# BaseBand.net
KiCad netlist of a schematic drawn in Altium Designer
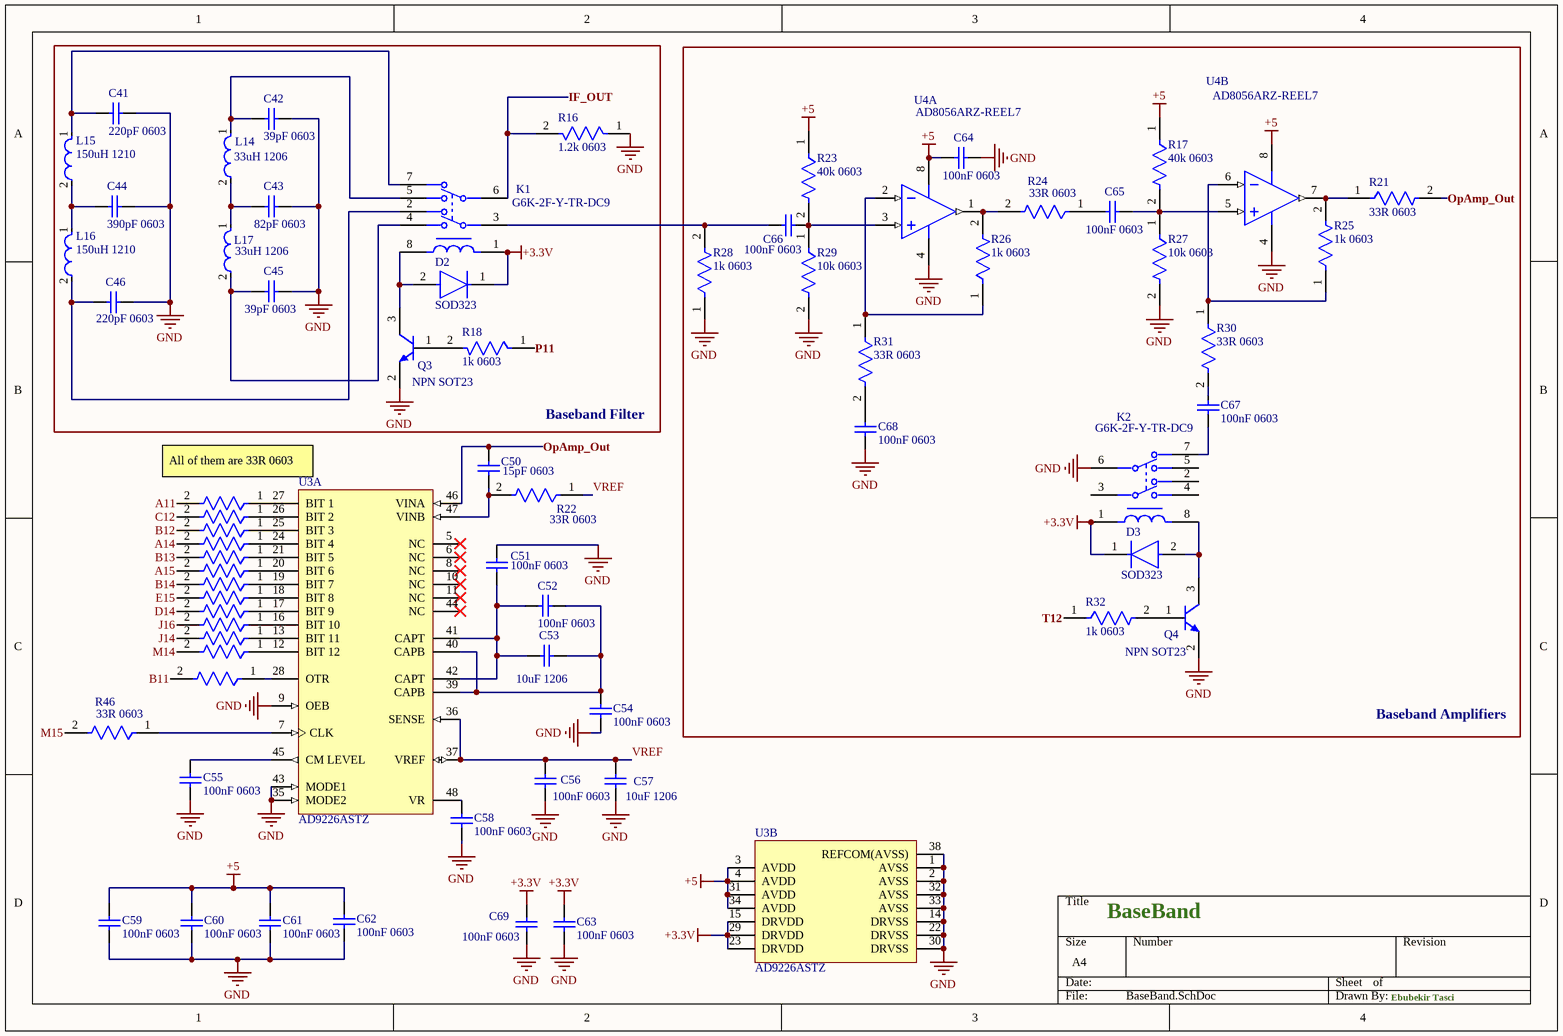
[diagram p0: BaseBand.SchDoc]

(export (version "E")
  (design (tool "Eeschema 10.0.6"))
  (components
    (comp (ref "C41")
      (value "220pF 0603")
      (footprint "CAPC1608X92X38LL15T08")
      (fields (field (name "MANUFACTURER") "Vitramon") (field (name "PART NUMBER") "VJ0603A101FXAAC"))
      (libsource (lib "Altium Content Vault") (part "CAP"))
    )
    (comp (ref "C42")
      (value "39pF 0603")
      (footprint "CAPC1608X92X38LL15T08")
      (fields (field (name "MANUFACTURER") "Vitramon") (field (name "PART NUMBER") "VJ0603A101FXAAC"))
      (libsource (lib "Altium Content Vault") (part "CAP"))
    )
    (comp (ref "C43")
      (value "82pF 0603")
      (footprint "CAPC1608X92X38LL15T08")
      (fields (field (name "MANUFACTURER") "Vitramon") (field (name "PART NUMBER") "VJ0603A101FXAAC"))
      (libsource (lib "Altium Content Vault") (part "CAP"))
    )
    (comp (ref "C44")
      (value "390pF 0603")
      (footprint "CAPC1608X92X38LL15T08")
      (fields (field (name "MANUFACTURER") "Vitramon") (field (name "PART NUMBER") "VJ0603A101FXAAC"))
      (libsource (lib "Altium Content Vault") (part "CAP"))
    )
    (comp (ref "C45")
      (value "39pF 0603")
      (footprint "CAPC1608X92X38LL15T08")
      (fields (field (name "MANUFACTURER") "Vitramon") (field (name "PART NUMBER") "VJ0603A101FXAAC"))
      (libsource (lib "Altium Content Vault") (part "CAP"))
    )
    (comp (ref "C46")
      (value "220pF 0603")
      (footprint "CAPC1608X92X38LL15T08")
      (fields (field (name "MANUFACTURER") "Vitramon") (field (name "PART NUMBER") "VJ0603A101FXAAC"))
      (libsource (lib "Altium Content Vault") (part "CAP"))
    )
    (comp (ref "C50")
      (value "15pF 0603")
      (footprint "CAPC1608X92X38LL15T08")
      (fields (field (name "MANUFACTURER") "Vitramon") (field (name "PART NUMBER") "VJ0603A101FXAAC"))
      (libsource (lib "Altium Content Vault") (part "CAP"))
    )
    (comp (ref "C51")
      (value "100nF 0603")
      (footprint "CAPC0603(1608)100_L")
      (description "CAP 100nF 16V ±0.1pF 0603 (1608 Metric) Thickness 1mm SMD")
      (fields (field (name "TOLERANCE") "Â±0.1pF"))
      (libsource (lib "Altium Content Vault") (part "CAP"))
    )
    (comp (ref "C52")
      (value "100nF 0603")
      (footprint "CAPC0603(1608)100_L")
      (description "CAP 100nF 16V ±0.1pF 0603 (1608 Metric) Thickness 1mm SMD")
      (fields (field (name "TOLERANCE") "Â±0.1pF"))
      (libsource (lib "Altium Content Vault") (part "CAP"))
    )
    (comp (ref "C53")
      (value "10uF 1206")
      (footprint "CAPC1206(3216)190_M")
      (description "CAP 10uF 16V ±5% 1206 (3216 Metric) Thickness 1.9mm SMD")
      (fields (field (name "TOLERANCE") "Â±5%"))
      (libsource (lib "Altium Content Vault") (part "CAP"))
    )
    (comp (ref "C54")
      (value "100nF 0603")
      (footprint "CAPC0603(1608)100_L")
      (description "CAP 100nF 16V ±0.1pF 0603 (1608 Metric) Thickness 1mm SMD")
      (fields (field (name "TOLERANCE") "Â±0.1pF"))
      (libsource (lib "Altium Content Vault") (part "CAP"))
    )
    (comp (ref "C55")
      (value "100nF 0603")
      (footprint "CAPC0603(1608)100_L")
      (description "CAP 100nF 16V ±0.1pF 0603 (1608 Metric) Thickness 1mm SMD")
      (fields (field (name "TOLERANCE") "Â±0.1pF"))
      (libsource (lib "Altium Content Vault") (part "CAP"))
    )
    (comp (ref "C56")
      (value "100nF 0603")
      (footprint "CAPC0603(1608)100_L")
      (description "CAP 100nF 16V ±0.1pF 0603 (1608 Metric) Thickness 1mm SMD")
      (fields (field (name "TOLERANCE") "Â±0.1pF"))
      (libsource (lib "Altium Content Vault") (part "CAP"))
    )
    (comp (ref "C57")
      (value "10uF 1206")
      (footprint "CAPC1206(3216)190_M")
      (description "CAP 10uF 16V ±5% 1206 (3216 Metric) Thickness 1.9mm SMD")
      (fields (field (name "TOLERANCE") "Â±5%"))
      (libsource (lib "Altium Content Vault") (part "CAP"))
    )
    (comp (ref "C58")
      (value "100nF 0603")
      (footprint "CAPC0603(1608)100_L")
      (description "CAP 100nF 16V ±0.1pF 0603 (1608 Metric) Thickness 1mm SMD")
      (fields (field (name "TOLERANCE") "Â±0.1pF"))
      (libsource (lib "Altium Content Vault") (part "CAP"))
    )
    (comp (ref "C59")
      (value "100nF 0603")
      (footprint "CAPC0603(1608)100_L")
      (description "CAP 100nF 16V ±0.1pF 0603 (1608 Metric) Thickness 1mm SMD")
      (fields (field (name "TOLERANCE") "Â±0.1pF"))
      (libsource (lib "Altium Content Vault") (part "CAP"))
    )
    (comp (ref "C60")
      (value "100nF 0603")
      (footprint "CAPC0603(1608)100_L")
      (description "CAP 100nF 16V ±0.1pF 0603 (1608 Metric) Thickness 1mm SMD")
      (fields (field (name "TOLERANCE") "Â±0.1pF"))
      (libsource (lib "Altium Content Vault") (part "CAP"))
    )
    (comp (ref "C61")
      (value "100nF 0603")
      (footprint "CAPC0603(1608)100_L")
      (description "CAP 100nF 16V ±0.1pF 0603 (1608 Metric) Thickness 1mm SMD")
      (fields (field (name "TOLERANCE") "Â±0.1pF"))
      (libsource (lib "Altium Content Vault") (part "CAP"))
    )
    (comp (ref "C62")
      (value "100nF 0603")
      (footprint "CAPC0603(1608)100_L")
      (description "CAP 100nF 16V ±0.1pF 0603 (1608 Metric) Thickness 1mm SMD")
      (fields (field (name "TOLERANCE") "Â±0.1pF"))
      (libsource (lib "Altium Content Vault") (part "CAP"))
    )
    (comp (ref "C63")
      (value "100nF 0603")
      (footprint "CAPC0603(1608)100_L")
      (description "CAP 100nF 16V ±0.1pF 0603 (1608 Metric) Thickness 1mm SMD")
      (fields (field (name "TOLERANCE") "Â±0.1pF"))
      (libsource (lib "Altium Content Vault") (part "CAP"))
    )
    (comp (ref "C64")
      (value "100nF 0603")
      (footprint "CAPC0603(1608)100_L")
      (description "CAP 100nF 16V ±0.1pF 0603 (1608 Metric) Thickness 1mm SMD")
      (fields (field (name "TOLERANCE") "Â±0.1pF"))
      (libsource (lib "Altium Content Vault") (part "CAP"))
    )
    (comp (ref "C65")
      (value "100nF 0603")
      (footprint "CAPC0603(1608)100_L")
      (description "CAP 100nF 16V ±0.1pF 0603 (1608 Metric) Thickness 1mm SMD")
      (fields (field (name "TOLERANCE") "Â±0.1pF"))
      (libsource (lib "Altium Content Vault") (part "CAP"))
    )
    (comp (ref "C66")
      (value "100nF 0603")
      (footprint "CAPC0603(1608)100_L")
      (description "CAP 100nF 16V ±0.1pF 0603 (1608 Metric) Thickness 1mm SMD")
      (fields (field (name "TOLERANCE") "Â±0.1pF"))
      (libsource (lib "Altium Content Vault") (part "CAP"))
    )
    (comp (ref "C67")
      (value "100nF 0603")
      (footprint "CAPC0603(1608)100_L")
      (description "CAP 100nF 16V ±0.1pF 0603 (1608 Metric) Thickness 1mm SMD")
      (fields (field (name "TOLERANCE") "Â±0.1pF"))
      (libsource (lib "Altium Content Vault") (part "CAP"))
    )
    (comp (ref "C68")
      (value "100nF 0603")
      (footprint "CAPC0603(1608)100_L")
      (description "CAP 100nF 16V ±0.1pF 0603 (1608 Metric) Thickness 1mm SMD")
      (fields (field (name "TOLERANCE") "Â±0.1pF"))
      (libsource (lib "Altium Content Vault") (part "CAP"))
    )
    (comp (ref "C69")
      (value "100nF 0603")
      (footprint "CAPC0603(1608)100_L")
      (description "CAP 100nF 16V ±0.1pF 0603 (1608 Metric) Thickness 1mm SMD")
      (fields (field (name "TOLERANCE") "Â±0.1pF"))
      (libsource (lib "Altium Content Vault") (part "CAP"))
    )
    (comp (ref "D2")
      (value "SOD323")
      (footprint "FP-SOD323F-MFG")
      (description "DIODE GEN PURP 100V 250MA SOD323")
      (fields
        (field (name "MANUFACTURER PART NUMBER") "1N4148WSF-7")
        (field (name "MANUFACTURER") "Diodes Inc.")
      )
      (libsource (lib "Altium Content Vault") (part "d7152d700b627762746794eb795d46e"))
    )
    (comp (ref "D3")
      (value "SOD323")
      (footprint "FP-SOD323F-MFG")
      (description "DIODE GEN PURP 100V 250MA SOD323")
      (fields
        (field (name "MANUFACTURER PART NUMBER") "1N4148WSF-7")
        (field (name "MANUFACTURER") "Diodes Inc.")
      )
      (libsource (lib "Altium Content Vault") (part "d7152d700b627762746794eb795d46e"))
    )
    (comp (ref "K1")
      (value "G6K-2F-Y-TR-DC9")
      (footprint "FP-G6K-2F-Y-TR-DC9-MFG")
      (description "RELAY TELECOM DPDT 1A 9VDC")
      (libsource (lib "") (part "58c38101009d5ebbf9054263c5b66d6_1"))
    )
    (comp (ref "K2")
      (value "G6K-2F-Y-TR-DC9")
      (footprint "FP-G6K-2F-Y-TR-DC9-MFG")
      (description "RELAY TELECOM DPDT 1A 9VDC")
      (libsource (lib "Altium Content Vault") (part "58c38101009d5ebbf9054263c5b66d6"))
    )
    (comp (ref "L14")
      (value "33uH 1206")
      (footprint "FP-CB3225-IPC_A")
      (description "SMD Inductors 33uH ±10% 0.57A 0.533Ω 1210")
      (fields (field (name "TOLERANCE") "10%"))
      (libsource (lib "Altium Content Vault") (part "725321dda6339637d4d059423bc1c3c"))
    )
    (comp (ref "L15")
      (value "150uH 1210")
      (footprint "FP-LQH32CH_23-MFG")
      (description "Wire Wound Ferrite Inductor for General Circuits 150μH ±10% 9.3Ω 70mA 1210")
      (fields (field (name "TOLERANCE") "10%"))
      (libsource (lib "Altium Content Vault") (part "725321dda6339637d4d059423bc1c3c"))
    )
    (comp (ref "L16")
      (value "150uH 1210")
      (footprint "FP-LQH32CH_23-MFG")
      (description "Wire Wound Ferrite Inductor for General Circuits 150μH ±10% 9.3Ω 70mA 1210")
      (fields (field (name "TOLERANCE") "10%"))
      (libsource (lib "Altium Content Vault") (part "725321dda6339637d4d059423bc1c3c"))
    )
    (comp (ref "L17")
      (value "33uH 1206")
      (footprint "FP-CB3225-IPC_A")
      (description "SMD Inductors 33uH ±10% 0.57A 0.533Ω 1210")
      (fields (field (name "TOLERANCE") "10%"))
      (libsource (lib "Altium Content Vault") (part "725321dda6339637d4d059423bc1c3c"))
    )
    (comp (ref "Q3")
      (value "NPN SOT23")
      (footprint "ONSC-SOT-23-3-318-08_V")
      (description "VHF / UHF Transistor, NPN Silicon, 3-Pin SOT-23, Pb-Free, Tape and Reel")
      (fields (field (name "MANUFACTURER") "On Semiconductor") (field (name "PARTNUMBER") "NSVMMBTH10LT1G"))
      (libsource (lib "Altium Content Vault") (part "ONSC-NPN-B1E2C3-3"))
    )
    (comp (ref "Q4")
      (value "NPN SOT23")
      (footprint "ONSC-SOT-23-3-318-08_V")
      (description "VHF / UHF Transistor, NPN Silicon, 3-Pin SOT-23, Pb-Free, Tape and Reel")
      (fields (field (name "MANUFACTURER") "On Semiconductor") (field (name "PARTNUMBER") "NSVMMBTH10LT1G"))
      (libsource (lib "Altium Content Vault") (part "ONSC-NPN-B1E2C3-3"))
    )
    (comp (ref "R16")
      (value "1.2k 0603")
      (footprint "FP-CPF0603-MFG")
      (description "RES SMD 1.2kΩ 0.1% 1/16W 0603")
      (fields
        (field (name "OCTOPART") "https://octopart.com/cpf0603b430re1-te+connectivity-22738753")
        (field (name "MANUFACTURER PART NUMBER") "CPF0603B430RE1")
      )
      (libsource (lib "Altium Content Vault") (part "1029c3af85768c4190bb7ad29bc67b5"))
    )
    (comp (ref "R17")
      (value "40k 0603")
      (footprint "FP-CPF0603-MFG")
      (description "RES SMD 40kΩ 0.1% 1/16W 0603")
      (fields
        (field (name "OCTOPART") "https://octopart.com/cpf0603b430re1-te+connectivity-22738753")
        (field (name "MANUFACTURER PART NUMBER") "CPF0603B430RE1")
      )
      (libsource (lib "Altium Content Vault") (part "1029c3af85768c4190bb7ad29bc67b5"))
    )
    (comp (ref "R18")
      (value "1k 0603")
      (footprint "FP-CPF0603-MFG")
      (description "RES SMD 1kΩ 0.1% 1/16W 0603")
      (fields
        (field (name "OCTOPART") "https://octopart.com/cpf0603b430re1-te+connectivity-22738753")
        (field (name "MANUFACTURER PART NUMBER") "CPF0603B430RE1")
      )
      (libsource (lib "Altium Content Vault") (part "1029c3af85768c4190bb7ad29bc67b5"))
    )
    (comp (ref "R21")
      (value "33R 0603")
      (footprint "FP-CPF0603-MFG")
      (description "RES SMD 33Ω 0.1% 1/16W 0603")
      (fields (field (name "TOLERANCE") "0.1%") (field (name "MANUFACTURER") "TE Connectivity"))
      (libsource (lib "Altium Content Vault") (part "1029c3af85768c4190bb7ad29bc67b5"))
    )
    (comp (ref "R22")
      (value "33R 0603")
      (footprint "FP-CPF0603-MFG")
      (description "RES SMD 33Ω 0.1% 1/16W 0603")
      (fields (field (name "TOLERANCE") "0.1%") (field (name "MANUFACTURER") "TE Connectivity"))
      (libsource (lib "Altium Content Vault") (part "1029c3af85768c4190bb7ad29bc67b5"))
    )
    (comp (ref "R23")
      (value "40k 0603")
      (footprint "FP-CPF0603-MFG")
      (description "RES SMD 40kΩ 0.1% 1/16W 0603")
      (fields
        (field (name "OCTOPART") "https://octopart.com/cpf0603b430re1-te+connectivity-22738753")
        (field (name "MANUFACTURER PART NUMBER") "CPF0603B430RE1")
      )
      (libsource (lib "Altium Content Vault") (part "1029c3af85768c4190bb7ad29bc67b5"))
    )
    (comp (ref "R24")
      (value "33R 0603")
      (footprint "FP-CPF0603-MFG")
      (description "RES SMD 33Ω 0.1% 1/16W 0603")
      (fields
        (field (name "OCTOPART") "https://octopart.com/cpf0603b430re1-te+connectivity-22738753")
        (field (name "MANUFACTURER PART NUMBER") "CPF0603B430RE1")
      )
      (libsource (lib "Altium Content Vault") (part "1029c3af85768c4190bb7ad29bc67b5"))
    )
    (comp (ref "R25")
      (value "1k 0603")
      (footprint "FP-CPF0603-MFG")
      (description "RES SMD 1kΩ 0.1% 1/16W 0603")
      (fields
        (field (name "OCTOPART") "https://octopart.com/cpf0603b430re1-te+connectivity-22738753")
        (field (name "MANUFACTURER PART NUMBER") "CPF0603B430RE1")
      )
      (libsource (lib "Altium Content Vault") (part "1029c3af85768c4190bb7ad29bc67b5"))
    )
    (comp (ref "R26")
      (value "1k 0603")
      (footprint "FP-CPF0603-MFG")
      (description "RES SMD 1kΩ 0.1% 1/16W 0603")
      (fields
        (field (name "OCTOPART") "https://octopart.com/cpf0603b430re1-te+connectivity-22738753")
        (field (name "MANUFACTURER PART NUMBER") "CPF0603B430RE1")
      )
      (libsource (lib "Altium Content Vault") (part "1029c3af85768c4190bb7ad29bc67b5"))
    )
    (comp (ref "R27")
      (value "10k 0603")
      (footprint "FP-CPF0603-MFG")
      (description "RES SMD 10kΩ 0.1% 1/16W 0603")
      (fields
        (field (name "OCTOPART") "https://octopart.com/cpf0603b430re1-te+connectivity-22738753")
        (field (name "MANUFACTURER PART NUMBER") "CPF0603B430RE1")
      )
      (libsource (lib "Altium Content Vault") (part "1029c3af85768c4190bb7ad29bc67b5"))
    )
    (comp (ref "R28")
      (value "1k 0603")
      (footprint "FP-CPF0603-MFG")
      (description "RES SMD 1kΩ 0.1% 1/16W 0603")
      (fields
        (field (name "OCTOPART") "https://octopart.com/cpf0603b430re1-te+connectivity-22738753")
        (field (name "MANUFACTURER PART NUMBER") "CPF0603B430RE1")
      )
      (libsource (lib "Altium Content Vault") (part "1029c3af85768c4190bb7ad29bc67b5"))
    )
    (comp (ref "R29")
      (value "10k 0603")
      (footprint "FP-CPF0603-MFG")
      (description "RES SMD 10kΩ 0.1% 1/16W 0603")
      (fields
        (field (name "OCTOPART") "https://octopart.com/cpf0603b430re1-te+connectivity-22738753")
        (field (name "MANUFACTURER PART NUMBER") "CPF0603B430RE1")
      )
      (libsource (lib "Altium Content Vault") (part "1029c3af85768c4190bb7ad29bc67b5"))
    )
    (comp (ref "R30")
      (value "33R 0603")
      (footprint "FP-CPF0603-MFG")
      (description "RES SMD 33Ω 0.1% 1/16W 0603")
      (fields
        (field (name "OCTOPART") "https://octopart.com/cpf0603b430re1-te+connectivity-22738753")
        (field (name "MANUFACTURER PART NUMBER") "CPF0603B430RE1")
      )
      (libsource (lib "Altium Content Vault") (part "1029c3af85768c4190bb7ad29bc67b5"))
    )
    (comp (ref "R31")
      (value "33R 0603")
      (footprint "FP-CPF0603-MFG")
      (description "RES SMD 33Ω 0.1% 1/16W 0603")
      (fields
        (field (name "OCTOPART") "https://octopart.com/cpf0603b430re1-te+connectivity-22738753")
        (field (name "MANUFACTURER PART NUMBER") "CPF0603B430RE1")
      )
      (libsource (lib "Altium Content Vault") (part "1029c3af85768c4190bb7ad29bc67b5"))
    )
    (comp (ref "R32")
      (value "1k 0603")
      (footprint "FP-CPF0603-MFG")
      (description "RES SMD 1kΩ 0.1% 1/16W 0603")
      (fields
        (field (name "OCTOPART") "https://octopart.com/cpf0603b430re1-te+connectivity-22738753")
        (field (name "MANUFACTURER PART NUMBER") "CPF0603B430RE1")
      )
      (libsource (lib "Altium Content Vault") (part "1029c3af85768c4190bb7ad29bc67b5"))
    )
    (comp (ref "R33")
      (value "33R 0603")
      (footprint "FP-CPF0603-MFG")
      (description "RES SMD 33Ω 0.1% 1/16W 0603")
      (fields
        (field (name "OCTOPART") "https://octopart.com/cpf0603b430re1-te+connectivity-22738753")
        (field (name "MANUFACTURER PART NUMBER") "CPF0603B430RE1")
      )
      (libsource (lib "Altium Content Vault") (part "1029c3af85768c4190bb7ad29bc67b5"))
    )
    (comp (ref "R34")
      (value "33R 0603")
      (footprint "FP-CPF0603-MFG")
      (description "RES SMD 33Ω 0.1% 1/16W 0603")
      (fields
        (field (name "OCTOPART") "https://octopart.com/cpf0603b430re1-te+connectivity-22738753")
        (field (name "MANUFACTURER PART NUMBER") "CPF0603B430RE1")
      )
      (libsource (lib "Altium Content Vault") (part "1029c3af85768c4190bb7ad29bc67b5"))
    )
    (comp (ref "R35")
      (value "33R 0603")
      (footprint "FP-CPF0603-MFG")
      (description "RES SMD 33Ω 0.1% 1/16W 0603")
      (fields
        (field (name "OCTOPART") "https://octopart.com/cpf0603b430re1-te+connectivity-22738753")
        (field (name "MANUFACTURER PART NUMBER") "CPF0603B430RE1")
      )
      (libsource (lib "Altium Content Vault") (part "1029c3af85768c4190bb7ad29bc67b5"))
    )
    (comp (ref "R36")
      (value "33R 0603")
      (footprint "FP-CPF0603-MFG")
      (description "RES SMD 33Ω 0.1% 1/16W 0603")
      (fields
        (field (name "OCTOPART") "https://octopart.com/cpf0603b430re1-te+connectivity-22738753")
        (field (name "MANUFACTURER PART NUMBER") "CPF0603B430RE1")
      )
      (libsource (lib "Altium Content Vault") (part "1029c3af85768c4190bb7ad29bc67b5"))
    )
    (comp (ref "R37")
      (value "33R 0603")
      (footprint "FP-CPF0603-MFG")
      (description "RES SMD 33Ω 0.1% 1/16W 0603")
      (fields
        (field (name "OCTOPART") "https://octopart.com/cpf0603b430re1-te+connectivity-22738753")
        (field (name "MANUFACTURER PART NUMBER") "CPF0603B430RE1")
      )
      (libsource (lib "Altium Content Vault") (part "1029c3af85768c4190bb7ad29bc67b5"))
    )
    (comp (ref "R38")
      (value "33R 0603")
      (footprint "FP-CPF0603-MFG")
      (description "RES SMD 33Ω 0.1% 1/16W 0603")
      (fields
        (field (name "OCTOPART") "https://octopart.com/cpf0603b430re1-te+connectivity-22738753")
        (field (name "MANUFACTURER PART NUMBER") "CPF0603B430RE1")
      )
      (libsource (lib "Altium Content Vault") (part "1029c3af85768c4190bb7ad29bc67b5"))
    )
    (comp (ref "R39")
      (value "33R 0603")
      (footprint "FP-CPF0603-MFG")
      (description "RES SMD 33Ω 0.1% 1/16W 0603")
      (fields
        (field (name "OCTOPART") "https://octopart.com/cpf0603b430re1-te+connectivity-22738753")
        (field (name "MANUFACTURER PART NUMBER") "CPF0603B430RE1")
      )
      (libsource (lib "Altium Content Vault") (part "1029c3af85768c4190bb7ad29bc67b5"))
    )
    (comp (ref "R40")
      (value "33R 0603")
      (footprint "FP-CPF0603-MFG")
      (description "RES SMD 33Ω 0.1% 1/16W 0603")
      (fields
        (field (name "OCTOPART") "https://octopart.com/cpf0603b430re1-te+connectivity-22738753")
        (field (name "MANUFACTURER PART NUMBER") "CPF0603B430RE1")
      )
      (libsource (lib "Altium Content Vault") (part "1029c3af85768c4190bb7ad29bc67b5"))
    )
    (comp (ref "R41")
      (value "33R 0603")
      (footprint "FP-CPF0603-MFG")
      (description "RES SMD 33Ω 0.1% 1/16W 0603")
      (fields
        (field (name "OCTOPART") "https://octopart.com/cpf0603b430re1-te+connectivity-22738753")
        (field (name "MANUFACTURER PART NUMBER") "CPF0603B430RE1")
      )
      (libsource (lib "Altium Content Vault") (part "1029c3af85768c4190bb7ad29bc67b5"))
    )
    (comp (ref "R42")
      (value "33R 0603")
      (footprint "FP-CPF0603-MFG")
      (description "RES SMD 33Ω 0.1% 1/16W 0603")
      (fields
        (field (name "OCTOPART") "https://octopart.com/cpf0603b430re1-te+connectivity-22738753")
        (field (name "MANUFACTURER PART NUMBER") "CPF0603B430RE1")
      )
      (libsource (lib "Altium Content Vault") (part "1029c3af85768c4190bb7ad29bc67b5"))
    )
    (comp (ref "R43")
      (value "33R 0603")
      (footprint "FP-CPF0603-MFG")
      (description "RES SMD 33Ω 0.1% 1/16W 0603")
      (fields
        (field (name "OCTOPART") "https://octopart.com/cpf0603b430re1-te+connectivity-22738753")
        (field (name "MANUFACTURER PART NUMBER") "CPF0603B430RE1")
      )
      (libsource (lib "Altium Content Vault") (part "1029c3af85768c4190bb7ad29bc67b5"))
    )
    (comp (ref "R44")
      (value "33R 0603")
      (footprint "FP-CPF0603-MFG")
      (description "RES SMD 33Ω 0.1% 1/16W 0603")
      (fields
        (field (name "OCTOPART") "https://octopart.com/cpf0603b430re1-te+connectivity-22738753")
        (field (name "MANUFACTURER PART NUMBER") "CPF0603B430RE1")
      )
      (libsource (lib "Altium Content Vault") (part "1029c3af85768c4190bb7ad29bc67b5"))
    )
    (comp (ref "R45")
      (value "33R 0603")
      (footprint "FP-CPF0603-MFG")
      (description "RES SMD 33Ω 0.1% 1/16W 0603")
      (fields
        (field (name "OCTOPART") "https://octopart.com/cpf0603b430re1-te+connectivity-22738753")
        (field (name "MANUFACTURER PART NUMBER") "CPF0603B430RE1")
      )
      (libsource (lib "Altium Content Vault") (part "1029c3af85768c4190bb7ad29bc67b5"))
    )
    (comp (ref "R46")
      (value "33R 0603")
      (footprint "FP-CPF0603-MFG")
      (description "RES SMD 33Ω 0.1% 1/16W 0603")
      (fields
        (field (name "OCTOPART") "https://octopart.com/cpf0603b430re1-te+connectivity-22738753")
        (field (name "MANUFACTURER PART NUMBER") "CPF0603B430RE1")
      )
      (libsource (lib "Altium Content Vault") (part "1029c3af85768c4190bb7ad29bc67b5"))
    )
    (comp (ref "U3")
      (value "AD9226ASTZ")
      (footprint "ST-48_N")
      (fields (field (name "GENERIC PART NUMBER") "AD9226") (field (name "MANUFACTURER") "Analog Devices"))
      (libsource (lib "Altium Content Vault") (part "ADI-AD9226-ST-48"))
    )
    (comp (ref "U4")
      (value "AD8056ARZ-REEL7")
      (footprint "ADI-R-8_M")
      (fields (field (name "GENERIC PART NUMBER") "AD8056") (field (name "MANUFACTURER") "Analog Devices"))
      (libsource (lib "Altium Content Vault") (part "ADI-AD80XX-8"))
    )
  )
  (nets
    (net (code "1") (name "+3.3V") (class "Default")
      (node (ref "C63") (pin "1") (pinfunction "1_1") (pintype "passive"))
      (node (ref "C69") (pin "1") (pinfunction "1_1") (pintype "passive"))
      (node (ref "D2") (pin "1") (pinfunction "C_1") (pintype "passive"))
      (node (ref "D3") (pin "1") (pinfunction "C_1") (pintype "passive"))
      (node (ref "K1") (pin "1") (pinfunction "1_1") (pintype "passive"))
      (node (ref "K2") (pin "1") (pinfunction "1_1") (pintype "passive"))
      (node (ref "U3") (pin "15") (pinfunction "DRVDD_15") (pintype "power_in"))
      (node (ref "U3") (pin "23") (pinfunction "DRVDD_23") (pintype "power_in"))
      (node (ref "U3") (pin "29") (pinfunction "DRVDD_29") (pintype "power_in"))
    )
    (net (code "2") (name "+5") (class "Default")
      (node (ref "C59") (pin "1") (pinfunction "1_1") (pintype "passive"))
      (node (ref "C60") (pin "1") (pinfunction "1_1") (pintype "passive"))
      (node (ref "C61") (pin "1") (pinfunction "1_1") (pintype "passive"))
      (node (ref "C62") (pin "1") (pinfunction "1_1") (pintype "passive"))
      (node (ref "C64") (pin "2") (pinfunction "2_2") (pintype "passive"))
      (node (ref "R17") (pin "1") (pinfunction "1_1") (pintype "passive"))
      (node (ref "R23") (pin "1") (pinfunction "1_1") (pintype "passive"))
      (node (ref "U3") (pin "3") (pinfunction "AVDD_3") (pintype "power_in"))
      (node (ref "U3") (pin "31") (pinfunction "AVDD_31") (pintype "power_in"))
      (node (ref "U3") (pin "34") (pinfunction "AVDD_34") (pintype "power_in"))
      (node (ref "U3") (pin "4") (pinfunction "AVDD_4") (pintype "power_in"))
      (node (ref "U4") (pin "8") (pinfunction "+VS_8") (pintype "power_in"))
    )
    (net (code "3") (name "/A11") (class "Default")
      (node (ref "R33") (pin "2") (pinfunction "2_2") (pintype "passive"))
    )
    (net (code "4") (name "/A14") (class "Default")
      (node (ref "R36") (pin "2") (pinfunction "2_2") (pintype "passive"))
    )
    (net (code "5") (name "/A15") (class "Default")
      (node (ref "R38") (pin "2") (pinfunction "2_2") (pintype "passive"))
    )
    (net (code "6") (name "/B11") (class "Default")
      (node (ref "R45") (pin "2") (pinfunction "2_2") (pintype "passive"))
    )
    (net (code "7") (name "/B12") (class "Default")
      (node (ref "R35") (pin "2") (pinfunction "2_2") (pintype "passive"))
    )
    (net (code "8") (name "/B13") (class "Default")
      (node (ref "R37") (pin "2") (pinfunction "2_2") (pintype "passive"))
    )
    (net (code "9") (name "/B14") (class "Default")
      (node (ref "R39") (pin "2") (pinfunction "2_2") (pintype "passive"))
    )
    (net (code "10") (name "/C12") (class "Default")
      (node (ref "R34") (pin "2") (pinfunction "2_2") (pintype "passive"))
    )
    (net (code "11") (name "/D14") (class "Default")
      (node (ref "R41") (pin "2") (pinfunction "2_2") (pintype "passive"))
    )
    (net (code "12") (name "/E15") (class "Default")
      (node (ref "R40") (pin "2") (pinfunction "2_2") (pintype "passive"))
    )
    (net (code "13") (name "/IF_OUT") (class "Default")
      (node (ref "K1") (pin "6") (pinfunction "6_6") (pintype "passive"))
      (node (ref "R16") (pin "2") (pinfunction "2_2") (pintype "passive"))
    )
    (net (code "14") (name "/J14") (class "Default")
      (node (ref "R43") (pin "2") (pinfunction "2_2") (pintype "passive"))
    )
    (net (code "15") (name "/J16") (class "Default")
      (node (ref "R42") (pin "2") (pinfunction "2_2") (pintype "passive"))
    )
    (net (code "16") (name "/M14") (class "Default")
      (node (ref "R44") (pin "2") (pinfunction "2_2") (pintype "passive"))
    )
    (net (code "17") (name "/M15") (class "Default")
      (node (ref "R46") (pin "2") (pinfunction "2_2") (pintype "passive"))
    )
    (net (code "18") (name "/OpAmp_Out") (class "Default")
      (node (ref "C50") (pin "2") (pinfunction "2_2") (pintype "passive"))
      (node (ref "R21") (pin "2") (pinfunction "2_2") (pintype "passive"))
      (node (ref "U3") (pin "46") (pinfunction "VINA_46") (pintype "input"))
    )
    (net (code "19") (name "/P11") (class "Default")
      (node (ref "R18") (pin "1") (pinfunction "1_1") (pintype "passive"))
    )
    (net (code "20") (name "/T12") (class "Default")
      (node (ref "R32") (pin "1") (pinfunction "1_1") (pintype "passive"))
    )
    (net (code "21") (name "/VREF") (class "Default")
      (node (ref "C56") (pin "1") (pinfunction "1_1") (pintype "passive"))
      (node (ref "C57") (pin "2") (pinfunction "2_2") (pintype "passive"))
      (node (ref "R22") (pin "1") (pinfunction "1_1") (pintype "passive"))
      (node (ref "U3") (pin "36") (pinfunction "SENSE_36") (pintype "input"))
      (node (ref "U3") (pin "37") (pinfunction "VREF_37") (pintype "bidirectional"))
    )
    (net (code "22") (name "GND") (class "Default")
      (node (ref "C41") (pin "1") (pinfunction "1_1") (pintype "passive"))
      (node (ref "C42") (pin "1") (pinfunction "1_1") (pintype "passive"))
      (node (ref "C43") (pin "1") (pinfunction "1_1") (pintype "passive"))
      (node (ref "C44") (pin "1") (pinfunction "1_1") (pintype "passive"))
      (node (ref "C45") (pin "1") (pinfunction "1_1") (pintype "passive"))
      (node (ref "C46") (pin "1") (pinfunction "1_1") (pintype "passive"))
      (node (ref "C51") (pin "2") (pinfunction "2_2") (pintype "passive"))
      (node (ref "C54") (pin "1") (pinfunction "1_1") (pintype "passive"))
      (node (ref "C55") (pin "2") (pinfunction "2_2") (pintype "passive"))
      (node (ref "C56") (pin "2") (pinfunction "2_2") (pintype "passive"))
      (node (ref "C57") (pin "1") (pinfunction "1_1") (pintype "passive"))
      (node (ref "C58") (pin "2") (pinfunction "2_2") (pintype "passive"))
      (node (ref "C59") (pin "2") (pinfunction "2_2") (pintype "passive"))
      (node (ref "C60") (pin "2") (pinfunction "2_2") (pintype "passive"))
      (node (ref "C61") (pin "2") (pinfunction "2_2") (pintype "passive"))
      (node (ref "C62") (pin "2") (pinfunction "2_2") (pintype "passive"))
      (node (ref "C63") (pin "2") (pinfunction "2_2") (pintype "passive"))
      (node (ref "C64") (pin "1") (pinfunction "1_1") (pintype "passive"))
      (node (ref "C68") (pin "2") (pinfunction "2_2") (pintype "passive"))
      (node (ref "C69") (pin "2") (pinfunction "2_2") (pintype "passive"))
      (node (ref "K2") (pin "6") (pinfunction "6_6") (pintype "passive"))
      (node (ref "Q3") (pin "2") (pinfunction "E_2") (pintype "passive"))
      (node (ref "Q4") (pin "2") (pinfunction "E_2") (pintype "passive"))
      (node (ref "R16") (pin "1") (pinfunction "1_1") (pintype "passive"))
      (node (ref "R27") (pin "2") (pinfunction "2_2") (pintype "passive"))
      (node (ref "R28") (pin "1") (pinfunction "1_1") (pintype "passive"))
      (node (ref "R29") (pin "2") (pinfunction "2_2") (pintype "passive"))
      (node (ref "U3") (pin "1") (pinfunction "AVSS_1") (pintype "power_in"))
      (node (ref "U3") (pin "14") (pinfunction "DRVSS_14") (pintype "power_in"))
      (node (ref "U3") (pin "2") (pinfunction "AVSS_2") (pintype "power_in"))
      (node (ref "U3") (pin "22") (pinfunction "DRVSS_22") (pintype "power_in"))
      (node (ref "U3") (pin "30") (pinfunction "DRVSS_30") (pintype "power_in"))
      (node (ref "U3") (pin "32") (pinfunction "AVSS_32") (pintype "power_in"))
      (node (ref "U3") (pin "33") (pinfunction "AVSS_33") (pintype "power_in"))
      (node (ref "U3") (pin "35") (pinfunction "MODE2_35") (pintype "input"))
      (node (ref "U3") (pin "38") (pinfunction "REFCOM(AVSS)_38") (pintype "power_in"))
      (node (ref "U3") (pin "43") (pinfunction "MODE1_43") (pintype "input"))
      (node (ref "U3") (pin "9") (pinfunction "OEB_9") (pintype "input"))
      (node (ref "U4") (pin "4") (pinfunction "-VS_4") (pintype "power_in"))
    )
    (net (code "23") (name "Net-(C41-Pad2)") (class "Default")
      (node (ref "C41") (pin "2") (pinfunction "2_2") (pintype "passive"))
      (node (ref "K1") (pin "7") (pinfunction "7_7") (pintype "passive"))
      (node (ref "L15") (pin "1") (pinfunction "1_1") (pintype "passive"))
    )
    (net (code "24") (name "Net-(C42-Pad2)") (class "Default")
      (node (ref "C42") (pin "2") (pinfunction "2_2") (pintype "passive"))
      (node (ref "K1") (pin "5") (pinfunction "5_5") (pintype "passive"))
      (node (ref "L14") (pin "1") (pinfunction "1_1") (pintype "passive"))
    )
    (net (code "25") (name "Net-(C43-Pad2)") (class "Default")
      (node (ref "C43") (pin "2") (pinfunction "2_2") (pintype "passive"))
      (node (ref "L14") (pin "2") (pinfunction "2_2") (pintype "passive"))
      (node (ref "L17") (pin "1") (pinfunction "1_1") (pintype "passive"))
    )
    (net (code "26") (name "Net-(C44-Pad2)") (class "Default")
      (node (ref "C44") (pin "2") (pinfunction "2_2") (pintype "passive"))
      (node (ref "L15") (pin "2") (pinfunction "2_2") (pintype "passive"))
      (node (ref "L16") (pin "1") (pinfunction "1_1") (pintype "passive"))
    )
    (net (code "27") (name "Net-(C45-Pad2)") (class "Default")
      (node (ref "C45") (pin "2") (pinfunction "2_2") (pintype "passive"))
      (node (ref "K1") (pin "4") (pinfunction "4_4") (pintype "passive"))
      (node (ref "L17") (pin "2") (pinfunction "2_2") (pintype "passive"))
    )
    (net (code "28") (name "Net-(C46-Pad2)") (class "Default")
      (node (ref "C46") (pin "2") (pinfunction "2_2") (pintype "passive"))
      (node (ref "K1") (pin "2") (pinfunction "2_2") (pintype "passive"))
      (node (ref "L16") (pin "2") (pinfunction "2_2") (pintype "passive"))
    )
    (net (code "29") (name "Net-(C51-Pad1)") (class "Default")
      (node (ref "C51") (pin "1") (pinfunction "1_1") (pintype "passive"))
      (node (ref "C52") (pin "1") (pinfunction "1_1") (pintype "passive"))
      (node (ref "C53") (pin "2") (pinfunction "2_2") (pintype "passive"))
      (node (ref "U3") (pin "41") (pinfunction "CAPT_41") (pintype "passive"))
      (node (ref "U3") (pin "42") (pinfunction "CAPT_42") (pintype "passive"))
    )
    (net (code "30") (name "Net-(C52-Pad2)") (class "Default")
      (node (ref "C52") (pin "2") (pinfunction "2_2") (pintype "passive"))
      (node (ref "C53") (pin "1") (pinfunction "1_1") (pintype "passive"))
      (node (ref "C54") (pin "2") (pinfunction "2_2") (pintype "passive"))
      (node (ref "U3") (pin "39") (pinfunction "CAPB_39") (pintype "passive"))
      (node (ref "U3") (pin "40") (pinfunction "CAPB_40") (pintype "passive"))
    )
    (net (code "31") (name "Net-(C65-Pad2)") (class "Default")
      (node (ref "C65") (pin "2") (pinfunction "2_2") (pintype "passive"))
      (node (ref "R24") (pin "1") (pinfunction "1_1") (pintype "passive"))
    )
    (net (code "32") (name "Net-(C66-Pad2)") (class "Default")
      (node (ref "C66") (pin "2") (pinfunction "2_2") (pintype "passive"))
      (node (ref "K1") (pin "3") (pinfunction "3_3") (pintype "passive"))
      (node (ref "R28") (pin "2") (pinfunction "2_2") (pintype "passive"))
    )
    (net (code "33") (name "Net-(C67-Pad1)") (class "Default")
      (node (ref "C67") (pin "1") (pinfunction "1_1") (pintype "passive"))
      (node (ref "R30") (pin "2") (pinfunction "2_2") (pintype "passive"))
    )
    (net (code "34") (name "Net-(C67-Pad2)") (class "Default")
      (node (ref "C67") (pin "2") (pinfunction "2_2") (pintype "passive"))
      (node (ref "K2") (pin "7") (pinfunction "7_7") (pintype "passive"))
    )
    (net (code "35") (name "Net-(C68-Pad1)") (class "Default")
      (node (ref "C68") (pin "1") (pinfunction "1_1") (pintype "passive"))
      (node (ref "R31") (pin "2") (pinfunction "2_2") (pintype "passive"))
    )
    (net (code "36") (name "Net-(D2-A)") (class "Default")
      (node (ref "D2") (pin "2") (pinfunction "A_2") (pintype "passive"))
      (node (ref "K1") (pin "8") (pinfunction "8_8") (pintype "passive"))
      (node (ref "Q3") (pin "3") (pinfunction "C_3") (pintype "passive"))
    )
    (net (code "37") (name "Net-(D3-A)") (class "Default")
      (node (ref "D3") (pin "2") (pinfunction "A_2") (pintype "passive"))
      (node (ref "K2") (pin "8") (pinfunction "8_8") (pintype "passive"))
      (node (ref "Q4") (pin "3") (pinfunction "C_3") (pintype "passive"))
    )
    (net (code "38") (name "Net-(Q3-B)") (class "Default")
      (node (ref "Q3") (pin "1") (pinfunction "B_1") (pintype "passive"))
      (node (ref "R18") (pin "2") (pinfunction "2_2") (pintype "passive"))
    )
    (net (code "39") (name "Net-(Q4-B)") (class "Default")
      (node (ref "Q4") (pin "1") (pinfunction "B_1") (pintype "passive"))
      (node (ref "R32") (pin "2") (pinfunction "2_2") (pintype "passive"))
    )
    (net (code "40") (name "Net-(U3A-BIT_1)") (class "Default")
      (node (ref "R33") (pin "1") (pinfunction "1_1") (pintype "passive"))
      (node (ref "U3") (pin "27") (pinfunction "BIT_1_27") (pintype "tri_state"))
    )
    (net (code "41") (name "Net-(U3A-BIT_2)") (class "Default")
      (node (ref "R34") (pin "1") (pinfunction "1_1") (pintype "passive"))
      (node (ref "U3") (pin "26") (pinfunction "BIT_2_26") (pintype "tri_state"))
    )
    (net (code "42") (name "Net-(U3A-BIT_3)") (class "Default")
      (node (ref "R35") (pin "1") (pinfunction "1_1") (pintype "passive"))
      (node (ref "U3") (pin "25") (pinfunction "BIT_3_25") (pintype "tri_state"))
    )
    (net (code "43") (name "Net-(U3A-BIT_4)") (class "Default")
      (node (ref "R36") (pin "1") (pinfunction "1_1") (pintype "passive"))
      (node (ref "U3") (pin "24") (pinfunction "BIT_4_24") (pintype "tri_state"))
    )
    (net (code "44") (name "Net-(U3A-BIT_5)") (class "Default")
      (node (ref "R37") (pin "1") (pinfunction "1_1") (pintype "passive"))
      (node (ref "U3") (pin "21") (pinfunction "BIT_5_21") (pintype "tri_state"))
    )
    (net (code "45") (name "Net-(U3A-BIT_6)") (class "Default")
      (node (ref "R38") (pin "1") (pinfunction "1_1") (pintype "passive"))
      (node (ref "U3") (pin "20") (pinfunction "BIT_6_20") (pintype "tri_state"))
    )
    (net (code "46") (name "Net-(U3A-BIT_7)") (class "Default")
      (node (ref "R39") (pin "1") (pinfunction "1_1") (pintype "passive"))
      (node (ref "U3") (pin "19") (pinfunction "BIT_7_19") (pintype "tri_state"))
    )
    (net (code "47") (name "Net-(U3A-BIT_8)") (class "Default")
      (node (ref "R40") (pin "1") (pinfunction "1_1") (pintype "passive"))
      (node (ref "U3") (pin "18") (pinfunction "BIT_8_18") (pintype "tri_state"))
    )
    (net (code "48") (name "Net-(U3A-BIT_9)") (class "Default")
      (node (ref "R41") (pin "1") (pinfunction "1_1") (pintype "passive"))
      (node (ref "U3") (pin "17") (pinfunction "BIT_9_17") (pintype "tri_state"))
    )
    (net (code "49") (name "Net-(U3A-BIT_10)") (class "Default")
      (node (ref "R42") (pin "1") (pinfunction "1_1") (pintype "passive"))
      (node (ref "U3") (pin "16") (pinfunction "BIT_10_16") (pintype "tri_state"))
    )
    (net (code "50") (name "Net-(U3A-BIT_11)") (class "Default")
      (node (ref "R43") (pin "1") (pinfunction "1_1") (pintype "passive"))
      (node (ref "U3") (pin "13") (pinfunction "BIT_11_13") (pintype "tri_state"))
    )
    (net (code "51") (name "Net-(U3A-BIT_12)") (class "Default")
      (node (ref "R44") (pin "1") (pinfunction "1_1") (pintype "passive"))
      (node (ref "U3") (pin "12") (pinfunction "BIT_12_12") (pintype "tri_state"))
    )
    (net (code "52") (name "Net-(U3A-CLK)") (class "Default")
      (node (ref "R46") (pin "1") (pinfunction "1_1") (pintype "passive"))
      (node (ref "U3") (pin "7") (pinfunction "CLK_7") (pintype "input"))
    )
    (net (code "53") (name "Net-(U3A-CM_LEVEL)") (class "Default")
      (node (ref "C55") (pin "1") (pinfunction "1_1") (pintype "passive"))
      (node (ref "U3") (pin "45") (pinfunction "CM_LEVEL_45") (pintype "output"))
    )
    (net (code "54") (name "Net-(U3A-OTR)") (class "Default")
      (node (ref "R45") (pin "1") (pinfunction "1_1") (pintype "passive"))
      (node (ref "U3") (pin "28") (pinfunction "OTR_28") (pintype "tri_state"))
    )
    (net (code "55") (name "Net-(U3A-VINB)") (class "Default")
      (node (ref "C50") (pin "1") (pinfunction "1_1") (pintype "passive"))
      (node (ref "R22") (pin "2") (pinfunction "2_2") (pintype "passive"))
      (node (ref "U3") (pin "47") (pinfunction "VINB_47") (pintype "input"))
    )
    (net (code "56") (name "Net-(U3A-VR)") (class "Default")
      (node (ref "C58") (pin "1") (pinfunction "1_1") (pintype "passive"))
      (node (ref "U3") (pin "48") (pinfunction "VR_48") (pintype "passive"))
    )
    (net (code "57") (name "Net-(U4A-+IN_1)") (class "Default")
      (node (ref "C66") (pin "1") (pinfunction "1_1") (pintype "passive"))
      (node (ref "R23") (pin "2") (pinfunction "2_2") (pintype "passive"))
      (node (ref "R29") (pin "1") (pinfunction "1_1") (pintype "passive"))
      (node (ref "U4") (pin "3") (pinfunction "+IN_1_3") (pintype "input"))
    )
    (net (code "58") (name "Net-(U4A--IN_1)") (class "Default")
      (node (ref "R26") (pin "1") (pinfunction "1_1") (pintype "passive"))
      (node (ref "R31") (pin "1") (pinfunction "1_1") (pintype "passive"))
      (node (ref "U4") (pin "2") (pinfunction "-IN_1_2") (pintype "input"))
    )
    (net (code "59") (name "Net-(U4A-OUT_1)") (class "Default")
      (node (ref "R24") (pin "2") (pinfunction "2_2") (pintype "passive"))
      (node (ref "R26") (pin "2") (pinfunction "2_2") (pintype "passive"))
      (node (ref "U4") (pin "1") (pinfunction "OUT_1_1") (pintype "output"))
    )
    (net (code "60") (name "Net-(U4B-+IN_2)") (class "Default")
      (node (ref "C65") (pin "1") (pinfunction "1_1") (pintype "passive"))
      (node (ref "R17") (pin "2") (pinfunction "2_2") (pintype "passive"))
      (node (ref "R27") (pin "1") (pinfunction "1_1") (pintype "passive"))
      (node (ref "U4") (pin "5") (pinfunction "+IN_2_5") (pintype "input"))
    )
    (net (code "61") (name "Net-(U4B--IN_2)") (class "Default")
      (node (ref "R25") (pin "1") (pinfunction "1_1") (pintype "passive"))
      (node (ref "R30") (pin "1") (pinfunction "1_1") (pintype "passive"))
      (node (ref "U4") (pin "6") (pinfunction "-IN_2_6") (pintype "input"))
    )
    (net (code "62") (name "Net-(U4B-OUT_2)") (class "Default")
      (node (ref "R21") (pin "1") (pinfunction "1_1") (pintype "passive"))
      (node (ref "R25") (pin "2") (pinfunction "2_2") (pintype "passive"))
      (node (ref "U4") (pin "7") (pinfunction "OUT_2_7") (pintype "output"))
    )
    (net (code "63") (name "unconnected-(K2-Pad2)") (class "Default")
      (node (ref "K2") (pin "2") (pinfunction "2_2") (pintype "passive"))
    )
    (net (code "64") (name "unconnected-(K2-Pad3)") (class "Default")
      (node (ref "K2") (pin "3") (pinfunction "3_3") (pintype "passive"))
    )
    (net (code "65") (name "unconnected-(K2-Pad4)") (class "Default")
      (node (ref "K2") (pin "4") (pinfunction "4_4") (pintype "passive"))
    )
    (net (code "66") (name "unconnected-(K2-Pad5)") (class "Default")
      (node (ref "K2") (pin "5") (pinfunction "5_5") (pintype "passive"))
    )
    (net (code "67") (name "unconnected-(U3A-NC-Pad5)") (class "Default")
      (node (ref "U3") (pin "5") (pinfunction "NC_5") (pintype "passive+no_connect"))
    )
    (net (code "68") (name "unconnected-(U3A-NC-Pad6)") (class "Default")
      (node (ref "U3") (pin "6") (pinfunction "NC_6") (pintype "passive+no_connect"))
    )
    (net (code "69") (name "unconnected-(U3A-NC-Pad8)") (class "Default")
      (node (ref "U3") (pin "8") (pinfunction "NC_8") (pintype "passive+no_connect"))
    )
    (net (code "70") (name "unconnected-(U3A-NC-Pad10)") (class "Default")
      (node (ref "U3") (pin "10") (pinfunction "NC_10") (pintype "passive+no_connect"))
    )
    (net (code "71") (name "unconnected-(U3A-NC-Pad11)") (class "Default")
      (node (ref "U3") (pin "11") (pinfunction "NC_11") (pintype "passive+no_connect"))
    )
    (net (code "72") (name "unconnected-(U3A-NC-Pad44)") (class "Default")
      (node (ref "U3") (pin "44") (pinfunction "NC_44") (pintype "passive+no_connect"))
    )
  )
)
